# esp8266-board.net
KiCad netlist of a schematic drawn in EAGLE
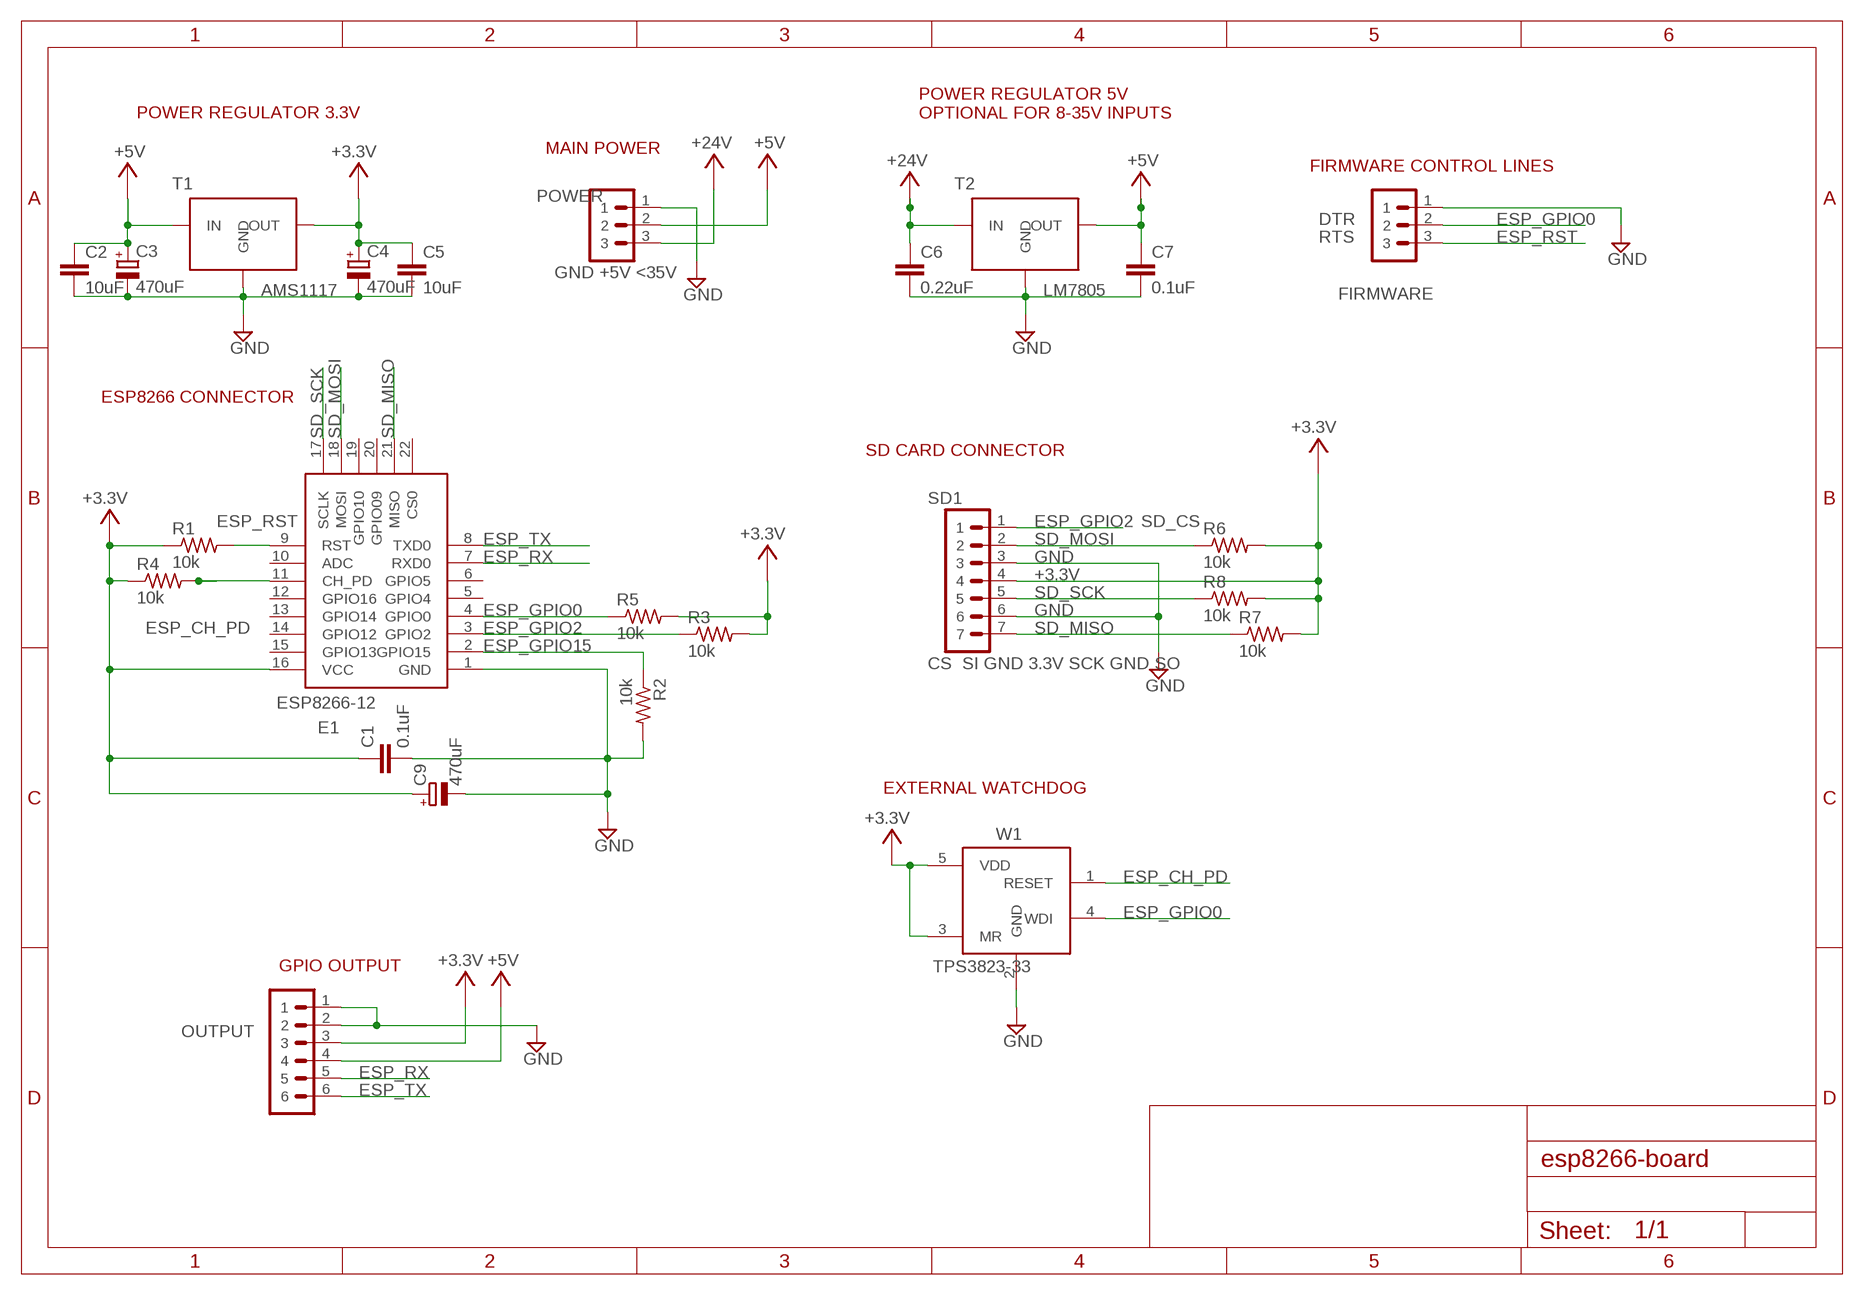
[diagram p0: schematic, sheet 1]

(export (version "E")
  (design (tool "Eeschema 10.0.6"))
  (components
    (comp (ref "C1")
      (value "0.1uF")
      (footprint "eagle-import:C2.5-2")
      (libsource (lib "eagle-import") (part "C2.5/2"))
    )
    (comp (ref "C2")
      (value "10uF")
      (footprint "eagle-import:C2.5-2")
      (libsource (lib "eagle-import") (part "C2.5/2"))
    )
    (comp (ref "C3")
      (value "470uF")
      (footprint "eagle-import:E2,5-6E")
      (libsource (lib "eagle-import") (part "CPOL-EUE2,5-6E"))
    )
    (comp (ref "C4")
      (value "470uF")
      (footprint "eagle-import:E2,5-6E")
      (fields (field (name "MPN") "FK18X5R0J106M"))
      (libsource (lib "eagle-import") (part "CPOL-EUE2,5-6E"))
    )
    (comp (ref "C5")
      (value "10uF")
      (footprint "eagle-import:C2.5-2")
      (libsource (lib "eagle-import") (part "C2.5/2"))
    )
    (comp (ref "C6")
      (value "0.22uF")
      (footprint "eagle-import:C2.5-2")
      (fields (field (name "MPN") "1C10Z5U104M050B"))
      (libsource (lib "eagle-import") (part "C2.5/2"))
    )
    (comp (ref "C7")
      (value "0.1uF")
      (footprint "eagle-import:C2.5-2")
      (fields (field (name "MPN") "FK18X5R0J106M"))
      (libsource (lib "eagle-import") (part "C2.5/2"))
    )
    (comp (ref "C9")
      (value "470uF")
      (footprint "eagle-import:E2,5-6")
      (libsource (lib "eagle-import") (part "CPOL-EUE2.5-6"))
    )
    (comp (ref "E1")
      (value "ESP8266-12")
      (footprint "eagle-import:ESP8266-12")
      (libsource (lib "eagle-import") (part "ESP8266-12"))
    )
    (comp (ref "FIRMWARE")
      (value "GND DTR RTS")
      (footprint "eagle-import:PIN-HEADER-3PIN")
      (libsource (lib "eagle-import") (part "PIN-HEADER-3PIN"))
    )
    (comp (ref "OUTPUT")
      (value "GND GND 3.3V 5V RX TX")
      (footprint "eagle-import:PIN-HEADER-6PIN")
      (libsource (lib "eagle-import") (part "PIN-HEADER-6PIN"))
    )
    (comp (ref "POWER")
      (value "GND +5V <35V")
      (footprint "eagle-import:PIN-HEADER-3PIN")
      (libsource (lib "eagle-import") (part "PIN-HEADER-3PIN"))
    )
    (comp (ref "R1")
      (value "10k")
      (footprint "eagle-import:RESISTOR-V1")
      (libsource (lib "eagle-import") (part "RESISTORV1"))
    )
    (comp (ref "R2")
      (value "10k")
      (footprint "eagle-import:RESISTOR-V1")
      (libsource (lib "eagle-import") (part "RESISTORV1"))
    )
    (comp (ref "R3")
      (value "10k")
      (footprint "eagle-import:RESISTOR-V1")
      (libsource (lib "eagle-import") (part "RESISTORV1"))
    )
    (comp (ref "R4")
      (value "10k")
      (footprint "eagle-import:RESISTOR-V1")
      (libsource (lib "eagle-import") (part "RESISTORV1"))
    )
    (comp (ref "R5")
      (value "10k")
      (footprint "eagle-import:RESISTOR-V1")
      (libsource (lib "eagle-import") (part "RESISTORV1"))
    )
    (comp (ref "R6")
      (value "10k")
      (footprint "eagle-import:RESISTOR-V1")
      (libsource (lib "eagle-import") (part "RESISTORV1"))
    )
    (comp (ref "R7")
      (value "10k")
      (footprint "eagle-import:RESISTOR-V1")
      (libsource (lib "eagle-import") (part "RESISTORV1"))
    )
    (comp (ref "R8")
      (value "10k")
      (footprint "eagle-import:RESISTOR-V1")
      (libsource (lib "eagle-import") (part "RESISTORV1"))
    )
    (comp (ref "SD1")
      (value "CS SI GND 3.3V SCK GND SO")
      (footprint "eagle-import:PIN-HEADER-7PIN")
      (libsource (lib "eagle-import") (part "PIN-HEADER-7PIN"))
    )
    (comp (ref "T1")
      (value "AMS1117")
      (footprint "eagle-import:SOT-223")
      (fields (field (name "MPN") "LM2937ET-3.3"))
      (libsource (lib "eagle-import") (part "AMS1117"))
    )
    (comp (ref "T2")
      (value "LM7805")
      (footprint "eagle-import:TO-220")
      (fields (field (name "MPN") "LM2937ET-3.3"))
      (libsource (lib "eagle-import") (part "LM7805"))
    )
    (comp (ref "W1")
      (value "TPS3823-33")
      (footprint "eagle-import:SOT23-5_TSOT25")
      (libsource (lib "eagle-import") (part "TPS382X"))
    )
  )
  (nets
    (net (code "1") (name "+3.3V") (class "Default")
      (node (ref "C1") (pin "1") (pinfunction "1_1") (pintype "passive"))
      (node (ref "C4") (pin "+") (pinfunction "+_+") (pintype "passive"))
      (node (ref "C5") (pin "1") (pinfunction "1_1") (pintype "passive"))
      (node (ref "C9") (pin "+") (pinfunction "+_+") (pintype "passive"))
      (node (ref "E1") (pin "16") (pinfunction "VCC_16") (pintype "input"))
      (node (ref "OUTPUT") (pin "3") (pinfunction "3_3") (pintype "passive"))
      (node (ref "R1") (pin "1") (pinfunction "1_1") (pintype "passive"))
      (node (ref "R3") (pin "2") (pinfunction "2_2") (pintype "passive"))
      (node (ref "R4") (pin "1") (pinfunction "1_1") (pintype "passive"))
      (node (ref "R5") (pin "2") (pinfunction "2_2") (pintype "passive"))
      (node (ref "R6") (pin "2") (pinfunction "2_2") (pintype "passive"))
      (node (ref "R7") (pin "2") (pinfunction "2_2") (pintype "passive"))
      (node (ref "R8") (pin "2") (pinfunction "2_2") (pintype "passive"))
      (node (ref "SD1") (pin "4") (pinfunction "4_4") (pintype "passive"))
      (node (ref "T1") (pin "2") (pinfunction "OUT_2") (pintype "power_in"))
      (node (ref "W1") (pin "3") (pinfunction "MR_3") (pintype "input"))
      (node (ref "W1") (pin "5") (pinfunction "VDD_5") (pintype "power_in"))
    )
    (net (code "2") (name "+5V") (class "Default")
      (node (ref "C2") (pin "1") (pinfunction "1_1") (pintype "passive"))
      (node (ref "C3") (pin "+") (pinfunction "+_+") (pintype "passive"))
      (node (ref "C7") (pin "1") (pinfunction "1_1") (pintype "passive"))
      (node (ref "OUTPUT") (pin "4") (pinfunction "4_4") (pintype "passive"))
      (node (ref "POWER") (pin "2") (pinfunction "2_2") (pintype "passive"))
      (node (ref "T1") (pin "3") (pinfunction "IN_3") (pintype "power_in"))
      (node (ref "T2") (pin "OUTPUT") (pinfunction "OUT_OUTPUT") (pintype "power_in"))
    )
    (net (code "3") (name "+24V") (class "Default")
      (node (ref "C6") (pin "1") (pinfunction "1_1") (pintype "passive"))
      (node (ref "POWER") (pin "3") (pinfunction "3_3") (pintype "passive"))
      (node (ref "T2") (pin "INPUT") (pinfunction "IN_INPUT") (pintype "power_in"))
    )
    (net (code "4") (name "/ESP_CH_PD") (class "Default")
      (node (ref "E1") (pin "11") (pinfunction "CH_PD_11") (pintype "input"))
      (node (ref "R4") (pin "2") (pinfunction "2_2") (pintype "passive"))
      (node (ref "W1") (pin "1") (pinfunction "RESET_1") (pintype "output"))
    )
    (net (code "5") (name "/ESP_GPIO0") (class "Default")
      (node (ref "E1") (pin "4") (pinfunction "GPIO0_4") (pintype "input"))
      (node (ref "FIRMWARE") (pin "2") (pinfunction "2_2") (pintype "passive"))
      (node (ref "R5") (pin "1") (pinfunction "1_1") (pintype "passive"))
      (node (ref "W1") (pin "4") (pinfunction "WDI_4") (pintype "input"))
    )
    (net (code "6") (name "/ESP_GPIO2") (class "Default")
      (node (ref "E1") (pin "3") (pinfunction "GPIO2_3") (pintype "input"))
      (node (ref "R3") (pin "1") (pinfunction "1_1") (pintype "passive"))
      (node (ref "SD1") (pin "1") (pinfunction "1_1") (pintype "passive"))
    )
    (net (code "7") (name "/ESP_GPIO15") (class "Default")
      (node (ref "E1") (pin "2") (pinfunction "GPIO15_2") (pintype "input"))
      (node (ref "R2") (pin "1") (pinfunction "1_1") (pintype "passive"))
    )
    (net (code "8") (name "/ESP_RST") (class "Default")
      (node (ref "E1") (pin "9") (pinfunction "RST_9") (pintype "input"))
      (node (ref "FIRMWARE") (pin "3") (pinfunction "3_3") (pintype "passive"))
      (node (ref "R1") (pin "2") (pinfunction "2_2") (pintype "passive"))
    )
    (net (code "9") (name "/ESP_RX") (class "Default")
      (node (ref "E1") (pin "7") (pinfunction "RXD0_7") (pintype "power_in"))
      (node (ref "OUTPUT") (pin "5") (pinfunction "5_5") (pintype "passive"))
    )
    (net (code "10") (name "/ESP_TX") (class "Default")
      (node (ref "E1") (pin "8") (pinfunction "TXD0_8") (pintype "bidirectional"))
      (node (ref "OUTPUT") (pin "6") (pinfunction "6_6") (pintype "passive"))
    )
    (net (code "11") (name "/GPIO5") (class "Default")
      (node (ref "E1") (pin "6") (pinfunction "GPIO5_6") (pintype "power_in"))
    )
    (net (code "12") (name "/SD_MISO") (class "Default")
      (node (ref "E1") (pin "21") (pinfunction "MISO_21") (pintype "bidirectional"))
      (node (ref "R7") (pin "1") (pinfunction "1_1") (pintype "passive"))
      (node (ref "SD1") (pin "7") (pinfunction "7_7") (pintype "passive"))
    )
    (net (code "13") (name "/SD_MOSI") (class "Default")
      (node (ref "E1") (pin "18") (pinfunction "MOSI_18") (pintype "bidirectional"))
      (node (ref "R6") (pin "1") (pinfunction "1_1") (pintype "passive"))
      (node (ref "SD1") (pin "2") (pinfunction "2_2") (pintype "passive"))
    )
    (net (code "14") (name "/SD_SCK") (class "Default")
      (node (ref "E1") (pin "17") (pinfunction "SCLK_17") (pintype "bidirectional"))
      (node (ref "R8") (pin "1") (pinfunction "1_1") (pintype "passive"))
      (node (ref "SD1") (pin "5") (pinfunction "5_5") (pintype "passive"))
    )
    (net (code "15") (name "GND") (class "Default")
      (node (ref "C1") (pin "2") (pinfunction "2_2") (pintype "passive"))
      (node (ref "C2") (pin "2") (pinfunction "2_2") (pintype "passive"))
      (node (ref "C3") (pin "-") (pinfunction "-_-") (pintype "passive"))
      (node (ref "C4") (pin "-") (pinfunction "-_-") (pintype "passive"))
      (node (ref "C5") (pin "2") (pinfunction "2_2") (pintype "passive"))
      (node (ref "C6") (pin "2") (pinfunction "2_2") (pintype "passive"))
      (node (ref "C7") (pin "2") (pinfunction "2_2") (pintype "passive"))
      (node (ref "C9") (pin "-") (pinfunction "-_-") (pintype "passive"))
      (node (ref "E1") (pin "1") (pinfunction "GND_1") (pintype "input"))
      (node (ref "FIRMWARE") (pin "1") (pinfunction "1_1") (pintype "passive"))
      (node (ref "OUTPUT") (pin "1") (pinfunction "1_1") (pintype "passive"))
      (node (ref "OUTPUT") (pin "2") (pinfunction "2_2") (pintype "passive"))
      (node (ref "POWER") (pin "1") (pinfunction "1_1") (pintype "passive"))
      (node (ref "R2") (pin "2") (pinfunction "2_2") (pintype "passive"))
      (node (ref "SD1") (pin "3") (pinfunction "3_3") (pintype "passive"))
      (node (ref "SD1") (pin "6") (pinfunction "6_6") (pintype "passive"))
      (node (ref "T1") (pin "1") (pinfunction "GND_1") (pintype "power_in"))
      (node (ref "T2") (pin "GND") (pinfunction "GND_GND") (pintype "power_in"))
      (node (ref "W1") (pin "2") (pinfunction "GND_2") (pintype "power_in"))
    )
    (net (code "16") (name "unconnected-(E1-ADC-Pad10)") (class "Default")
      (node (ref "E1") (pin "10") (pinfunction "ADC_10") (pintype "input"))
    )
    (net (code "17") (name "unconnected-(E1-CS0-Pad22)") (class "Default")
      (node (ref "E1") (pin "22") (pinfunction "CS0_22") (pintype "bidirectional"))
    )
    (net (code "18") (name "unconnected-(E1-GPIO4-Pad5)") (class "Default")
      (node (ref "E1") (pin "5") (pinfunction "GPIO4_5") (pintype "input"))
    )
    (net (code "19") (name "unconnected-(E1-GPIO09-Pad20)") (class "Default")
      (node (ref "E1") (pin "20") (pinfunction "GPIO09_20") (pintype "bidirectional"))
    )
    (net (code "20") (name "unconnected-(E1-GPIO10-Pad19)") (class "Default")
      (node (ref "E1") (pin "19") (pinfunction "GPIO10_19") (pintype "bidirectional"))
    )
    (net (code "21") (name "unconnected-(E1-GPIO12-Pad14)") (class "Default")
      (node (ref "E1") (pin "14") (pinfunction "GPIO12_14") (pintype "input"))
    )
    (net (code "22") (name "unconnected-(E1-GPIO13-Pad15)") (class "Default")
      (node (ref "E1") (pin "15") (pinfunction "GPIO13_15") (pintype "input"))
    )
    (net (code "23") (name "unconnected-(E1-GPIO14-Pad13)") (class "Default")
      (node (ref "E1") (pin "13") (pinfunction "GPIO14_13") (pintype "input"))
    )
    (net (code "24") (name "unconnected-(E1-GPIO16-Pad12)") (class "Default")
      (node (ref "E1") (pin "12") (pinfunction "GPIO16_12") (pintype "input"))
    )
  )
)
